# Preamp_Filter.net
KiCad netlist of a schematic drawn in Altium Designer
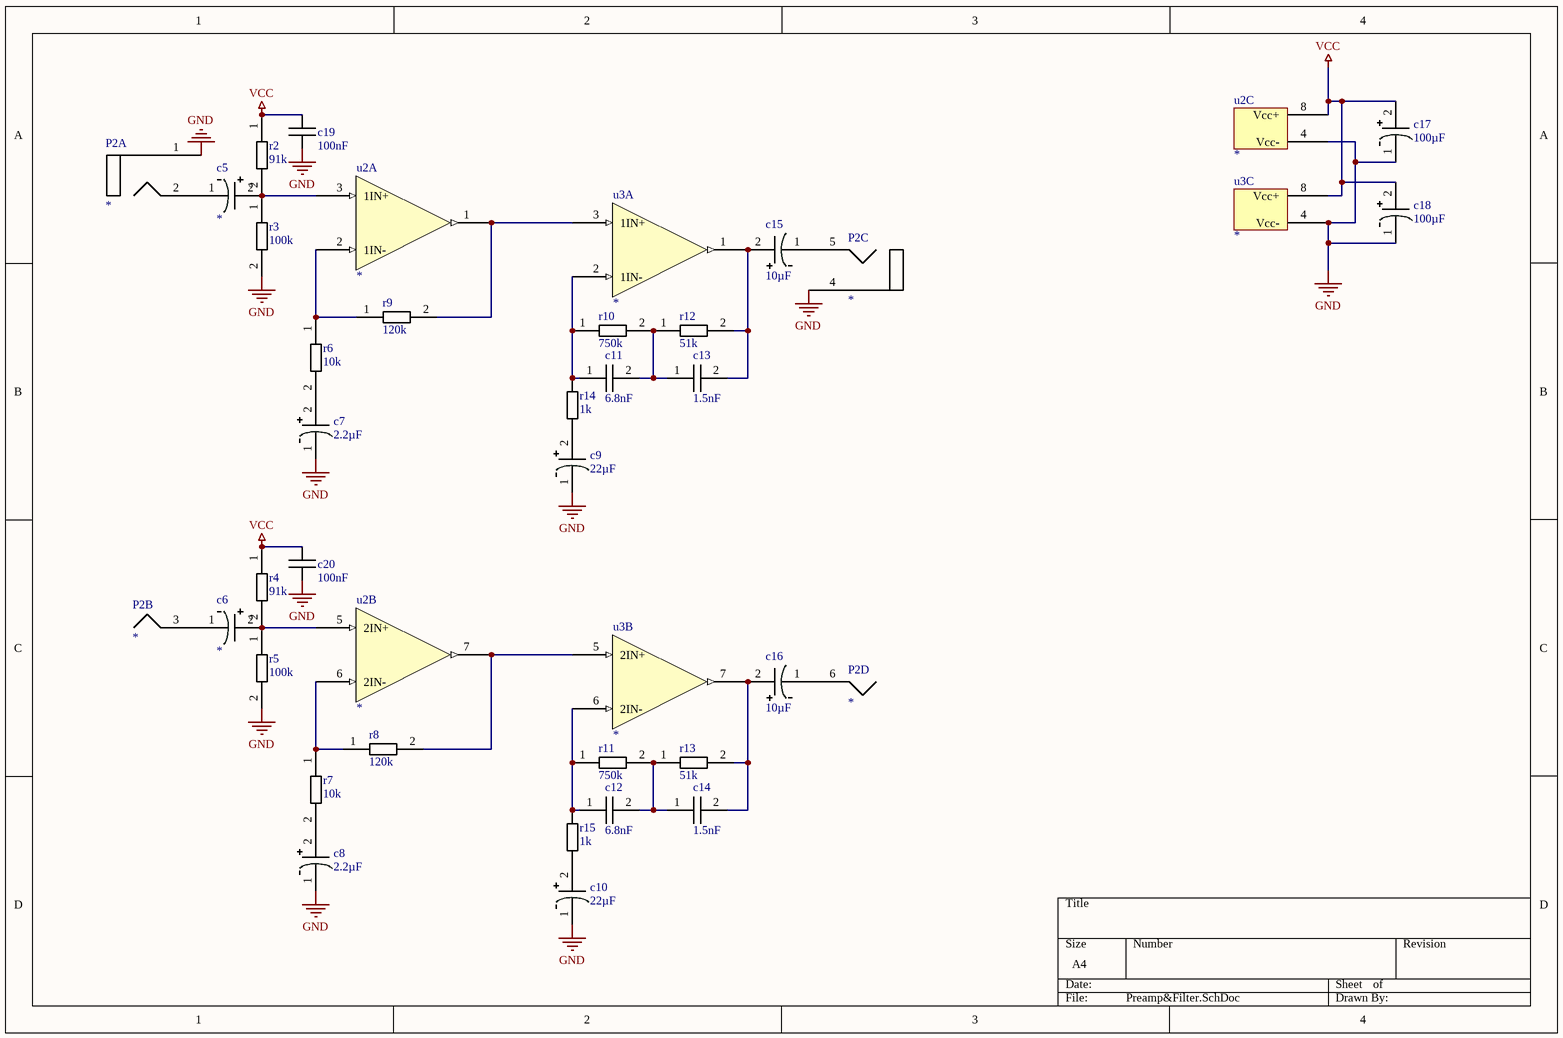
[diagram p0: Preamp&Filter.SchDoc]

(export (version "E")
  (design (tool "Eeschema 10.0.6"))
  (components
    (comp (ref "c5") (value "*") (footprint "Elco-B") (libsource (lib "") (part "Elco B_1")))
    (comp (ref "c6") (value "*") (footprint "Elco-B") (libsource (lib "") (part "Elco B_1")))
    (comp (ref "c7") (value "2.2µF") (footprint "Elco-B") (libsource (lib "Panasonic") (part "Elco B")))
    (comp (ref "c8") (value "2.2µF") (footprint "Elco-B") (libsource (lib "Panasonic") (part "Elco B")))
    (comp (ref "c9")
      (value "22µF")
      (footprint "Elco-D")
      (description "Elco size D 6.3x5.4")
      (libsource (lib "Panasonic") (part "Elco D"))
    )
    (comp (ref "c10")
      (value "22µF")
      (footprint "Elco-D")
      (description "Elco size D 6.3x5.4")
      (libsource (lib "Panasonic") (part "Elco D"))
    )
    (comp (ref "c11")
      (value "6.8nF")
      (footprint "0805")
      (description "0805 Capacitor Package")
      (libsource (lib "Generic R-C") (part "0805 Capacitor"))
    )
    (comp (ref "c12")
      (value "6.8nF")
      (footprint "0805")
      (description "0805 Capacitor Package")
      (libsource (lib "Generic R-C") (part "0805 Capacitor"))
    )
    (comp (ref "c13")
      (value "1.5nF")
      (footprint "0805")
      (description "0805 Capacitor Package")
      (libsource (lib "Generic R-C") (part "0805 Capacitor"))
    )
    (comp (ref "c14")
      (value "1.5nF")
      (footprint "0805")
      (description "0805 Capacitor Package")
      (libsource (lib "Generic R-C") (part "0805 Capacitor"))
    )
    (comp (ref "c15") (value "10µF") (footprint "Elco-C") (libsource (lib "Panasonic") (part "Elco C")))
    (comp (ref "c16") (value "10µF") (footprint "Elco-C") (libsource (lib "Panasonic") (part "Elco C")))
    (comp (ref "c17")
      (value "100µF")
      (footprint "Elco-D")
      (description "Elco size D 6.3x5.4")
      (libsource (lib "Panasonic") (part "Elco D"))
    )
    (comp (ref "c18")
      (value "100µF")
      (footprint "Elco-D")
      (description "Elco size D 6.3x5.4")
      (libsource (lib "Panasonic") (part "Elco D"))
    )
    (comp (ref "c19")
      (value "100nF")
      (footprint "0805")
      (description "...F")
      (libsource (lib "") (part "0805 Capacitor_1"))
    )
    (comp (ref "c20")
      (value "100nF")
      (footprint "0805")
      (description "...F")
      (libsource (lib "") (part "0805 Capacitor_1"))
    )
    (comp (ref "P2")
      (value "*")
      (footprint "RCA 4-way")
      (description "4-way RCA connector")
      (libsource (lib "Pro-Signal") (part "PSG01551"))
    )
    (comp (ref "r2")
      (value "91k")
      (footprint "0805")
      (description "0805 Resistor package")
      (libsource (lib "Generic R-C") (part "0805 Resistor"))
    )
    (comp (ref "r3")
      (value "100k")
      (footprint "0805")
      (description "0805 Resistor package")
      (libsource (lib "Generic R-C") (part "0805 Resistor"))
    )
    (comp (ref "r4")
      (value "91k")
      (footprint "0805")
      (description "0805 Resistor package")
      (libsource (lib "Generic R-C") (part "0805 Resistor"))
    )
    (comp (ref "r5")
      (value "100k")
      (footprint "0805")
      (description "0805 Resistor package")
      (libsource (lib "Generic R-C") (part "0805 Resistor"))
    )
    (comp (ref "r6")
      (value "10k")
      (footprint "0805")
      (description "0805 Resistor package")
      (libsource (lib "Generic R-C") (part "0805 Resistor"))
    )
    (comp (ref "r7")
      (value "10k")
      (footprint "0805")
      (description "0805 Resistor package")
      (libsource (lib "Generic R-C") (part "0805 Resistor"))
    )
    (comp (ref "r8")
      (value "120k")
      (footprint "0805")
      (description "0805 Resistor package")
      (libsource (lib "Generic R-C") (part "0805 Resistor"))
    )
    (comp (ref "r9")
      (value "120k")
      (footprint "0805")
      (description "0805 Resistor package")
      (libsource (lib "Generic R-C") (part "0805 Resistor"))
    )
    (comp (ref "r10")
      (value "750k")
      (footprint "0805")
      (description "0805 Resistor package")
      (libsource (lib "Generic R-C") (part "0805 Resistor"))
    )
    (comp (ref "r11")
      (value "750k")
      (footprint "0805")
      (description "0805 Resistor package")
      (libsource (lib "Generic R-C") (part "0805 Resistor"))
    )
    (comp (ref "r12")
      (value "51k")
      (footprint "0805")
      (description "0805 Resistor package")
      (libsource (lib "Generic R-C") (part "0805 Resistor"))
    )
    (comp (ref "r13")
      (value "51k")
      (footprint "0805")
      (description "0805 Resistor package")
      (libsource (lib "Generic R-C") (part "0805 Resistor"))
    )
    (comp (ref "r14")
      (value "1k")
      (footprint "0805")
      (description "...R")
      (libsource (lib "") (part "0805 Resistor_1"))
    )
    (comp (ref "r15")
      (value "1k")
      (footprint "0805")
      (description "...R")
      (libsource (lib "") (part "0805 Resistor_1"))
    )
    (comp (ref "u2")
      (value "*")
      (footprint "R-PDSO-G8-P127d620x530")
      (description "Dual Low-Noise OpAmp")
      (libsource (lib "Texas Instruments") (part "NE5532x"))
    )
    (comp (ref "u3")
      (value "*")
      (footprint "R-PDSO-G8-P127d620x530")
      (description "Low-Noise JFET-input OpAmp")
      (libsource (lib "Texas Instruments") (part "TL027x"))
    )
  )
  (nets
    (net (code "1") (name "GND") (class "Default")
      (node (ref "P2") (pin "1") (pintype "power_in"))
      (node (ref "P2") (pin "4") (pintype "power_in"))
      (node (ref "c10") (pin "1") (pintype "passive"))
      (node (ref "c17") (pin "1") (pintype "passive"))
      (node (ref "c18") (pin "1") (pintype "passive"))
      (node (ref "c19") (pin "1") (pintype "passive"))
      (node (ref "c20") (pin "1") (pintype "passive"))
      (node (ref "c7") (pin "1") (pintype "passive"))
      (node (ref "c8") (pin "1") (pintype "passive"))
      (node (ref "c9") (pin "1") (pintype "passive"))
      (node (ref "r3") (pin "2") (pintype "passive"))
      (node (ref "r5") (pin "2") (pintype "passive"))
      (node (ref "u2") (pin "4") (pinfunction "Vcc-_4") (pintype "power_in"))
      (node (ref "u3") (pin "4") (pinfunction "Vcc-_4") (pintype "power_in"))
    )
    (net (code "2") (name "Net-(P2-Pad2)") (class "Default")
      (node (ref "P2") (pin "2") (pintype "passive"))
      (node (ref "c5") (pin "1") (pintype "passive"))
    )
    (net (code "3") (name "Net-(P2-Pad3)") (class "Default")
      (node (ref "P2") (pin "3") (pintype "passive"))
      (node (ref "c6") (pin "1") (pintype "passive"))
    )
    (net (code "4") (name "Net-(P2-Pad5)") (class "Default")
      (node (ref "P2") (pin "5") (pintype "passive"))
      (node (ref "c15") (pin "1") (pintype "passive"))
    )
    (net (code "5") (name "Net-(P2-Pad6)") (class "Default")
      (node (ref "P2") (pin "6") (pintype "passive"))
      (node (ref "c16") (pin "1") (pintype "passive"))
    )
    (net (code "6") (name "Net-(c7-Pad2)") (class "Default")
      (node (ref "c7") (pin "2") (pintype "passive"))
      (node (ref "r6") (pin "2") (pintype "passive"))
    )
    (net (code "7") (name "Net-(c8-Pad2)") (class "Default")
      (node (ref "c8") (pin "2") (pintype "passive"))
      (node (ref "r7") (pin "2") (pintype "passive"))
    )
    (net (code "8") (name "Net-(c9-Pad2)") (class "Default")
      (node (ref "c9") (pin "2") (pintype "passive"))
      (node (ref "r14") (pin "1") (pintype "passive"))
    )
    (net (code "9") (name "Net-(c10-Pad2)") (class "Default")
      (node (ref "c10") (pin "2") (pintype "passive"))
      (node (ref "r15") (pin "1") (pintype "passive"))
    )
    (net (code "10") (name "Net-(c11-Pad2)") (class "Default")
      (node (ref "c11") (pin "2") (pintype "passive"))
      (node (ref "c13") (pin "1") (pintype "passive"))
      (node (ref "r10") (pin "2") (pintype "passive"))
      (node (ref "r12") (pin "1") (pintype "passive"))
    )
    (net (code "11") (name "Net-(c12-Pad2)") (class "Default")
      (node (ref "c12") (pin "2") (pintype "passive"))
      (node (ref "c14") (pin "1") (pintype "passive"))
      (node (ref "r11") (pin "2") (pintype "passive"))
      (node (ref "r13") (pin "1") (pintype "passive"))
    )
    (net (code "12") (name "Net-(u2A-1IN+)") (class "Default")
      (node (ref "c5") (pin "2") (pintype "passive"))
      (node (ref "r2") (pin "2") (pintype "passive"))
      (node (ref "r3") (pin "1") (pintype "passive"))
      (node (ref "u2") (pin "3") (pinfunction "1IN+_3") (pintype "input"))
    )
    (net (code "13") (name "Net-(u2A-1IN-)") (class "Default")
      (node (ref "r6") (pin "1") (pintype "passive"))
      (node (ref "r9") (pin "1") (pintype "passive"))
      (node (ref "u2") (pin "2") (pinfunction "1IN-_2") (pintype "input"))
    )
    (net (code "14") (name "Net-(u2A-1OUT)") (class "Default")
      (node (ref "r9") (pin "2") (pintype "passive"))
      (node (ref "u2") (pin "1") (pinfunction "1OUT_1") (pintype "output"))
      (node (ref "u3") (pin "3") (pinfunction "1IN+_3") (pintype "input"))
    )
    (net (code "15") (name "Net-(u2B-2IN+)") (class "Default")
      (node (ref "c6") (pin "2") (pintype "passive"))
      (node (ref "r4") (pin "2") (pintype "passive"))
      (node (ref "r5") (pin "1") (pintype "passive"))
      (node (ref "u2") (pin "5") (pinfunction "2IN+_5") (pintype "input"))
    )
    (net (code "16") (name "Net-(u2B-2IN-)") (class "Default")
      (node (ref "r7") (pin "1") (pintype "passive"))
      (node (ref "r8") (pin "1") (pintype "passive"))
      (node (ref "u2") (pin "6") (pinfunction "2IN-_6") (pintype "input"))
    )
    (net (code "17") (name "Net-(u2B-2OUT)") (class "Default")
      (node (ref "r8") (pin "2") (pintype "passive"))
      (node (ref "u2") (pin "7") (pinfunction "2OUT_7") (pintype "output"))
      (node (ref "u3") (pin "5") (pinfunction "2IN+_5") (pintype "input"))
    )
    (net (code "18") (name "Net-(u3A-1IN-)") (class "Default")
      (node (ref "c11") (pin "1") (pintype "passive"))
      (node (ref "r10") (pin "1") (pintype "passive"))
      (node (ref "r14") (pin "2") (pintype "passive"))
      (node (ref "u3") (pin "2") (pinfunction "1IN-_2") (pintype "input"))
    )
    (net (code "19") (name "Net-(u3A-1OUT)") (class "Default")
      (node (ref "c13") (pin "2") (pintype "passive"))
      (node (ref "c15") (pin "2") (pintype "passive"))
      (node (ref "r12") (pin "2") (pintype "passive"))
      (node (ref "u3") (pin "1") (pinfunction "1OUT_1") (pintype "output"))
    )
    (net (code "20") (name "Net-(u3B-2IN-)") (class "Default")
      (node (ref "c12") (pin "1") (pintype "passive"))
      (node (ref "r11") (pin "1") (pintype "passive"))
      (node (ref "r15") (pin "2") (pintype "passive"))
      (node (ref "u3") (pin "6") (pinfunction "2IN-_6") (pintype "input"))
    )
    (net (code "21") (name "Net-(u3B-2OUT)") (class "Default")
      (node (ref "c14") (pin "2") (pintype "passive"))
      (node (ref "c16") (pin "2") (pintype "passive"))
      (node (ref "r13") (pin "2") (pintype "passive"))
      (node (ref "u3") (pin "7") (pinfunction "2OUT_7") (pintype "output"))
    )
    (net (code "22") (name "VCC") (class "Default")
      (node (ref "c17") (pin "2") (pintype "passive"))
      (node (ref "c18") (pin "2") (pintype "passive"))
      (node (ref "c19") (pin "2") (pintype "passive"))
      (node (ref "c20") (pin "2") (pintype "passive"))
      (node (ref "r2") (pin "1") (pintype "passive"))
      (node (ref "r4") (pin "1") (pintype "passive"))
      (node (ref "u2") (pin "8") (pinfunction "Vcc+_8") (pintype "power_in"))
      (node (ref "u3") (pin "8") (pinfunction "Vcc+_8") (pintype "power_in"))
    )
  )
)
